# power_supply.net
KiCad netlist of a schematic drawn in EAGLE
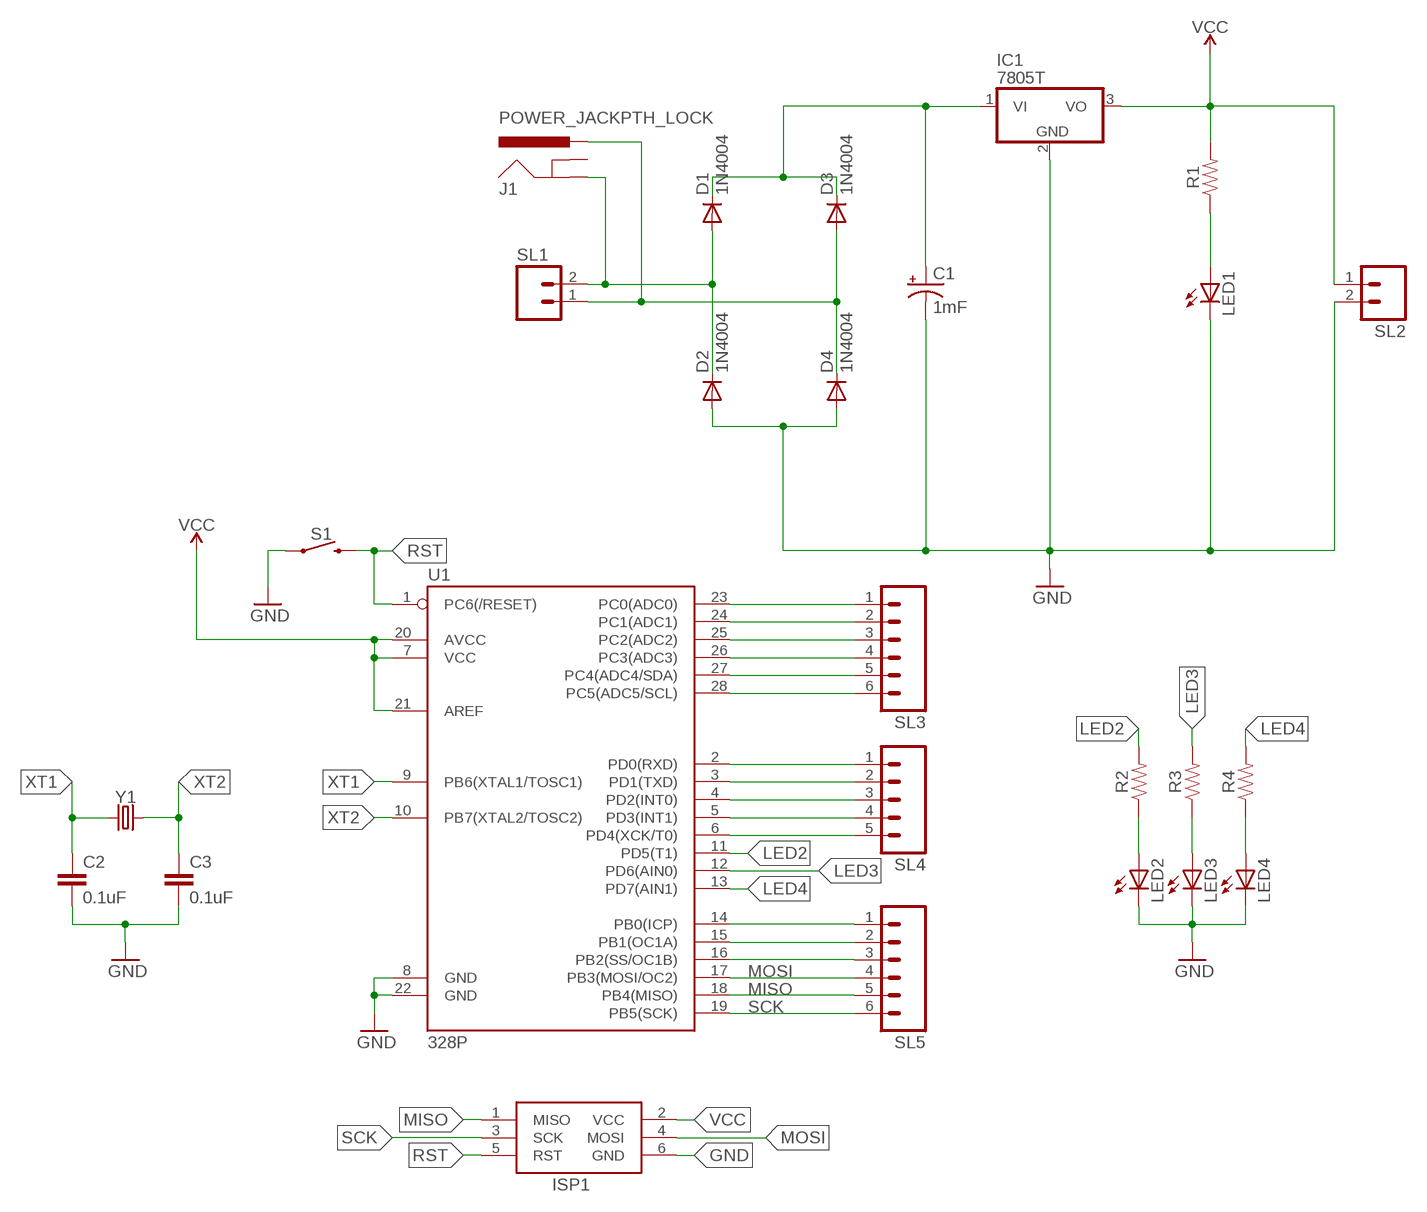
[diagram p0: schematic, sheet 1]

(export (version "E")
  (design (tool "Eeschema 10.0.6"))
  (components
    (comp (ref "C1")
      (value "1mF")
      (footprint "eagle-import:CPOL-RADIAL-5MM-10MM")
      (libsource (lib "eagle-import") (part "1000UF-RADIAL-5MM-25V-20%"))
    )
    (comp (ref "C2")
      (value "0.1uF")
      (footprint "eagle-import:CAP-PTH-SMALL-KIT")
      (libsource (lib "eagle-import") (part "0.1UF-KIT-EZ-50V-20%"))
    )
    (comp (ref "C3")
      (value "0.1uF")
      (footprint "eagle-import:CAP-PTH-SMALL-KIT")
      (libsource (lib "eagle-import") (part "0.1UF-KIT-EZ-50V-20%"))
    )
    (comp (ref "D1")
      (value "1N4004")
      (footprint "eagle-import:DO41-10")
      (libsource (lib "eagle-import") (part "1N4004"))
    )
    (comp (ref "D2")
      (value "1N4004")
      (footprint "eagle-import:DO41-10")
      (libsource (lib "eagle-import") (part "1N4004"))
    )
    (comp (ref "D3")
      (value "1N4004")
      (footprint "eagle-import:DO41-10")
      (libsource (lib "eagle-import") (part "1N4004"))
    )
    (comp (ref "D4")
      (value "1N4004")
      (footprint "eagle-import:DO41-10")
      (libsource (lib "eagle-import") (part "1N4004"))
    )
    (comp (ref "IC1")
      (value "7805T")
      (footprint "eagle-import:TO220H")
      (libsource (lib "eagle-import") (part "78T05"))
    )
    (comp (ref "ISP1")
      (value "AVRISP-6")
      (footprint "eagle-import:AVRISP")
      (libsource (lib "eagle-import") (part "AVRISP-6"))
    )
    (comp (ref "J1")
      (value "POWER_JACKPTH_LOCK")
      (footprint "eagle-import:POWER_JACK_PTH_LOCK")
      (libsource (lib "eagle-import") (part "POWER_JACKPTH_LOCK"))
    )
    (comp (ref "LED1")
      (value "LED5MM")
      (footprint "eagle-import:LED5MM")
      (libsource (lib "eagle-import") (part "LED5MM"))
    )
    (comp (ref "LED2")
      (value "LED3MM")
      (footprint "eagle-import:LED3MM")
      (libsource (lib "eagle-import") (part "LED3MM"))
    )
    (comp (ref "LED3")
      (value "LED3MM")
      (footprint "eagle-import:LED3MM")
      (libsource (lib "eagle-import") (part "LED3MM"))
    )
    (comp (ref "LED4")
      (value "LED3MM")
      (footprint "eagle-import:LED3MM")
      (libsource (lib "eagle-import") (part "LED3MM"))
    )
    (comp (ref "R1")
      (value "RESISTORAXIAL-0.3")
      (footprint "eagle-import:AXIAL-0.3")
      (libsource (lib "eagle-import") (part "RESISTORAXIAL-0.3"))
    )
    (comp (ref "R2")
      (value "RESISTORAXIAL-0.3")
      (footprint "eagle-import:AXIAL-0.3")
      (libsource (lib "eagle-import") (part "RESISTORAXIAL-0.3"))
    )
    (comp (ref "R3")
      (value "RESISTORAXIAL-0.3")
      (footprint "eagle-import:AXIAL-0.3")
      (libsource (lib "eagle-import") (part "RESISTORAXIAL-0.3"))
    )
    (comp (ref "R4")
      (value "RESISTORAXIAL-0.3")
      (footprint "eagle-import:AXIAL-0.3")
      (libsource (lib "eagle-import") (part "RESISTORAXIAL-0.3"))
    )
    (comp (ref "S1")
      (value "MOMENTARY-SWITCH-SPST-PTH-6.0MM")
      (footprint "eagle-import:TACTILE_SWITCH_PTH_6.0MM")
      (libsource (lib "eagle-import") (part "MOMENTARY-SWITCH-SPST-PTH-6.0MM"))
    )
    (comp (ref "SL1")
      (value "M02")
      (footprint "eagle-import:02P")
      (libsource (lib "eagle-import") (part "M02"))
    )
    (comp (ref "SL2")
      (value "M02")
      (footprint "eagle-import:02P")
      (libsource (lib "eagle-import") (part "M02"))
    )
    (comp (ref "SL3")
      (value "M06")
      (footprint "eagle-import:06P")
      (libsource (lib "eagle-import") (part "M06"))
    )
    (comp (ref "SL4")
      (value "M05")
      (footprint "eagle-import:05P")
      (libsource (lib "eagle-import") (part "M05"))
    )
    (comp (ref "SL5")
      (value "M06")
      (footprint "eagle-import:06P")
      (libsource (lib "eagle-import") (part "M06"))
    )
    (comp (ref "U1")
      (value "328P")
      (footprint "eagle-import:DIP28")
      (libsource (lib "eagle-import") (part "ATMEGA328P_PDIP"))
    )
    (comp (ref "Y1")
      (value "CRYSTALPTH-HC49US")
      (footprint "eagle-import:HC49US")
      (libsource (lib "eagle-import") (part "CRYSTALPTH-HC49US"))
    )
  )
  (nets
    (net (code "1") (name "GND") (class "Default")
      (node (ref "C1") (pin "-") (pinfunction "-_-") (pintype "passive"))
      (node (ref "C2") (pin "2") (pinfunction "2_2") (pintype "passive"))
      (node (ref "C3") (pin "2") (pinfunction "2_2") (pintype "passive"))
      (node (ref "D2") (pin "A") (pinfunction "A_A") (pintype "passive"))
      (node (ref "D4") (pin "A") (pinfunction "A_A") (pintype "passive"))
      (node (ref "IC1") (pin "2") (pinfunction "GND_2") (pintype "passive"))
      (node (ref "ISP1") (pin "6") (pinfunction "GND_6") (pintype "power_in"))
      (node (ref "LED1") (pin "K") (pinfunction "C_K") (pintype "passive"))
      (node (ref "LED2") (pin "K") (pinfunction "C_K") (pintype "passive"))
      (node (ref "LED3") (pin "K") (pinfunction "C_K") (pintype "passive"))
      (node (ref "LED4") (pin "K") (pinfunction "C_K") (pintype "passive"))
      (node (ref "S1") (pin "1") (pinfunction "1_1") (pintype "passive"))
      (node (ref "SL2") (pin "2") (pinfunction "2_2") (pintype "passive"))
      (node (ref "U1") (pin "22") (pinfunction "GND_22") (pintype "bidirectional"))
      (node (ref "U1") (pin "8") (pinfunction "GND_8") (pintype "bidirectional"))
    )
    (net (code "2") (name "LED2") (class "Default")
      (node (ref "R2") (pin "P$2") (pinfunction "2_P$2") (pintype "passive"))
      (node (ref "U1") (pin "11") (pinfunction "PD5(T1)_11") (pintype "bidirectional"))
    )
    (net (code "3") (name "LED3") (class "Default")
      (node (ref "R3") (pin "P$2") (pinfunction "2_P$2") (pintype "passive"))
      (node (ref "U1") (pin "12") (pinfunction "PD6(AIN0)_12") (pintype "bidirectional"))
    )
    (net (code "4") (name "LED4") (class "Default")
      (node (ref "R4") (pin "P$2") (pinfunction "2_P$2") (pintype "passive"))
      (node (ref "U1") (pin "13") (pinfunction "PD7(AIN1)_13") (pintype "bidirectional"))
    )
    (net (code "5") (name "MISO") (class "Default")
      (node (ref "ISP1") (pin "1") (pinfunction "MISO_1") (pintype "input"))
      (node (ref "SL5") (pin "5") (pinfunction "5_5") (pintype "passive"))
      (node (ref "U1") (pin "18") (pinfunction "PB4(MISO)_18") (pintype "bidirectional"))
    )
    (net (code "6") (name "MOSI") (class "Default")
      (node (ref "ISP1") (pin "4") (pinfunction "MOSI_4") (pintype "output"))
      (node (ref "SL5") (pin "4") (pinfunction "4_4") (pintype "passive"))
      (node (ref "U1") (pin "17") (pinfunction "PB3(MOSI/OC2)_17") (pintype "bidirectional"))
    )
    (net (code "7") (name "Net-(D1-PadA)") (class "Default")
      (node (ref "D1") (pin "A") (pinfunction "A_A") (pintype "passive"))
      (node (ref "D2") (pin "C") (pinfunction "C_C") (pintype "passive"))
      (node (ref "J1") (pin "GND") (pinfunction "GND_GND") (pintype "bidirectional"))
      (node (ref "SL1") (pin "2") (pinfunction "2_2") (pintype "passive"))
    )
    (net (code "8") (name "Net-(D3-PadA)") (class "Default")
      (node (ref "D3") (pin "A") (pinfunction "A_A") (pintype "passive"))
      (node (ref "D4") (pin "C") (pinfunction "C_C") (pintype "passive"))
      (node (ref "J1") (pin "PWR") (pinfunction "PWR_PWR") (pintype "bidirectional"))
      (node (ref "SL1") (pin "1") (pinfunction "1_1") (pintype "passive"))
    )
    (net (code "9") (name "Net-(IC1-VI)") (class "Default")
      (node (ref "C1") (pin "+") (pinfunction "+_+") (pintype "passive"))
      (node (ref "D1") (pin "C") (pinfunction "C_C") (pintype "passive"))
      (node (ref "D3") (pin "C") (pinfunction "C_C") (pintype "passive"))
      (node (ref "IC1") (pin "1") (pinfunction "VI_1") (pintype "input"))
    )
    (net (code "10") (name "Net-(R1-1)") (class "Default")
      (node (ref "LED1") (pin "A") (pinfunction "A_A") (pintype "passive"))
      (node (ref "R1") (pin "P$1") (pinfunction "1_P$1") (pintype "passive"))
    )
    (net (code "11") (name "Net-(R2-1)") (class "Default")
      (node (ref "LED2") (pin "A") (pinfunction "A_A") (pintype "passive"))
      (node (ref "R2") (pin "P$1") (pinfunction "1_P$1") (pintype "passive"))
    )
    (net (code "12") (name "Net-(R3-1)") (class "Default")
      (node (ref "LED3") (pin "A") (pinfunction "A_A") (pintype "passive"))
      (node (ref "R3") (pin "P$1") (pinfunction "1_P$1") (pintype "passive"))
    )
    (net (code "13") (name "Net-(R4-1)") (class "Default")
      (node (ref "LED4") (pin "A") (pinfunction "A_A") (pintype "passive"))
      (node (ref "R4") (pin "P$1") (pinfunction "1_P$1") (pintype "passive"))
    )
    (net (code "14") (name "Net-(U1-PB0(ICP))") (class "Default")
      (node (ref "SL5") (pin "1") (pinfunction "1_1") (pintype "passive"))
      (node (ref "U1") (pin "14") (pinfunction "PB0(ICP)_14") (pintype "bidirectional"))
    )
    (net (code "15") (name "Net-(U1-PB1(OC1A))") (class "Default")
      (node (ref "SL5") (pin "2") (pinfunction "2_2") (pintype "passive"))
      (node (ref "U1") (pin "15") (pinfunction "PB1(OC1A)_15") (pintype "bidirectional"))
    )
    (net (code "16") (name "Net-(U1-PB2(SS{slash}OC1B))") (class "Default")
      (node (ref "SL5") (pin "3") (pinfunction "3_3") (pintype "passive"))
      (node (ref "U1") (pin "16") (pinfunction "PB2(SS/OC1B)_16") (pintype "bidirectional"))
    )
    (net (code "17") (name "Net-(U1-PC0(ADC0))") (class "Default")
      (node (ref "SL3") (pin "1") (pinfunction "1_1") (pintype "passive"))
      (node (ref "U1") (pin "23") (pinfunction "PC0(ADC0)_23") (pintype "bidirectional"))
    )
    (net (code "18") (name "Net-(U1-PC1(ADC1))") (class "Default")
      (node (ref "SL3") (pin "2") (pinfunction "2_2") (pintype "passive"))
      (node (ref "U1") (pin "24") (pinfunction "PC1(ADC1)_24") (pintype "bidirectional"))
    )
    (net (code "19") (name "Net-(U1-PC2(ADC2))") (class "Default")
      (node (ref "SL3") (pin "3") (pinfunction "3_3") (pintype "passive"))
      (node (ref "U1") (pin "25") (pinfunction "PC2(ADC2)_25") (pintype "bidirectional"))
    )
    (net (code "20") (name "Net-(U1-PC3(ADC3))") (class "Default")
      (node (ref "SL3") (pin "4") (pinfunction "4_4") (pintype "passive"))
      (node (ref "U1") (pin "26") (pinfunction "PC3(ADC3)_26") (pintype "bidirectional"))
    )
    (net (code "21") (name "Net-(U1-PC4(ADC4{slash}SDA))") (class "Default")
      (node (ref "SL3") (pin "5") (pinfunction "5_5") (pintype "passive"))
      (node (ref "U1") (pin "27") (pinfunction "PC4(ADC4/SDA)_27") (pintype "bidirectional"))
    )
    (net (code "22") (name "Net-(U1-PC5(ADC5{slash}SCL))") (class "Default")
      (node (ref "SL3") (pin "6") (pinfunction "6_6") (pintype "passive"))
      (node (ref "U1") (pin "28") (pinfunction "PC5(ADC5/SCL)_28") (pintype "bidirectional"))
    )
    (net (code "23") (name "Net-(U1-PD0(RXD))") (class "Default")
      (node (ref "SL4") (pin "1") (pinfunction "1_1") (pintype "passive"))
      (node (ref "U1") (pin "2") (pinfunction "PD0(RXD)_2") (pintype "bidirectional"))
    )
    (net (code "24") (name "Net-(U1-PD1(TXD))") (class "Default")
      (node (ref "SL4") (pin "2") (pinfunction "2_2") (pintype "passive"))
      (node (ref "U1") (pin "3") (pinfunction "PD1(TXD)_3") (pintype "bidirectional"))
    )
    (net (code "25") (name "Net-(U1-PD2(INT0))") (class "Default")
      (node (ref "SL4") (pin "3") (pinfunction "3_3") (pintype "passive"))
      (node (ref "U1") (pin "4") (pinfunction "PD2(INT0)_4") (pintype "bidirectional"))
    )
    (net (code "26") (name "Net-(U1-PD3(INT1))") (class "Default")
      (node (ref "SL4") (pin "4") (pinfunction "4_4") (pintype "passive"))
      (node (ref "U1") (pin "5") (pinfunction "PD3(INT1)_5") (pintype "bidirectional"))
    )
    (net (code "27") (name "Net-(U1-PD4(XCK{slash}T0))") (class "Default")
      (node (ref "SL4") (pin "5") (pinfunction "5_5") (pintype "passive"))
      (node (ref "U1") (pin "6") (pinfunction "PD4(XCK/T0)_6") (pintype "bidirectional"))
    )
    (net (code "28") (name "RST") (class "Default")
      (node (ref "ISP1") (pin "5") (pinfunction "RST_5") (pintype "output"))
      (node (ref "S1") (pin "3") (pinfunction "2_3") (pintype "passive"))
      (node (ref "U1") (pin "1") (pinfunction "PC6(/RESET)_1") (pintype "bidirectional"))
    )
    (net (code "29") (name "SCK") (class "Default")
      (node (ref "ISP1") (pin "3") (pinfunction "SCK_3") (pintype "output"))
      (node (ref "SL5") (pin "6") (pinfunction "6_6") (pintype "passive"))
      (node (ref "U1") (pin "19") (pinfunction "PB5(SCK)_19") (pintype "bidirectional"))
    )
    (net (code "30") (name "VCC") (class "Default")
      (node (ref "IC1") (pin "3") (pinfunction "VO_3") (pintype "passive"))
      (node (ref "ISP1") (pin "2") (pinfunction "VCC_2") (pintype "power_in"))
      (node (ref "R1") (pin "P$2") (pinfunction "2_P$2") (pintype "passive"))
      (node (ref "SL2") (pin "1") (pinfunction "1_1") (pintype "passive"))
      (node (ref "U1") (pin "20") (pinfunction "AVCC_20") (pintype "bidirectional"))
      (node (ref "U1") (pin "21") (pinfunction "AREF_21") (pintype "bidirectional"))
      (node (ref "U1") (pin "7") (pinfunction "VCC_7") (pintype "bidirectional"))
    )
    (net (code "31") (name "XT1") (class "Default")
      (node (ref "C2") (pin "1") (pinfunction "1_1") (pintype "passive"))
      (node (ref "U1") (pin "9") (pinfunction "PB6(XTAL1/TOSC1)_9") (pintype "bidirectional"))
      (node (ref "Y1") (pin "1") (pinfunction "1_1") (pintype "passive"))
    )
    (net (code "32") (name "XT2") (class "Default")
      (node (ref "C3") (pin "1") (pinfunction "1_1") (pintype "passive"))
      (node (ref "U1") (pin "10") (pinfunction "PB7(XTAL2/TOSC2)_10") (pintype "bidirectional"))
      (node (ref "Y1") (pin "2") (pinfunction "2_2") (pintype "passive"))
    )
    (net (code "33") (name "unconnected-(J1-PadGNDBREAK)") (class "Default")
      (node (ref "J1") (pin "GNDBREAK") (pinfunction "GNDBREAK_GNDBREAK") (pintype "bidirectional"))
    )
  )
)
